# IMU_Core.net
KiCad netlist of a schematic drawn in Altium Designer
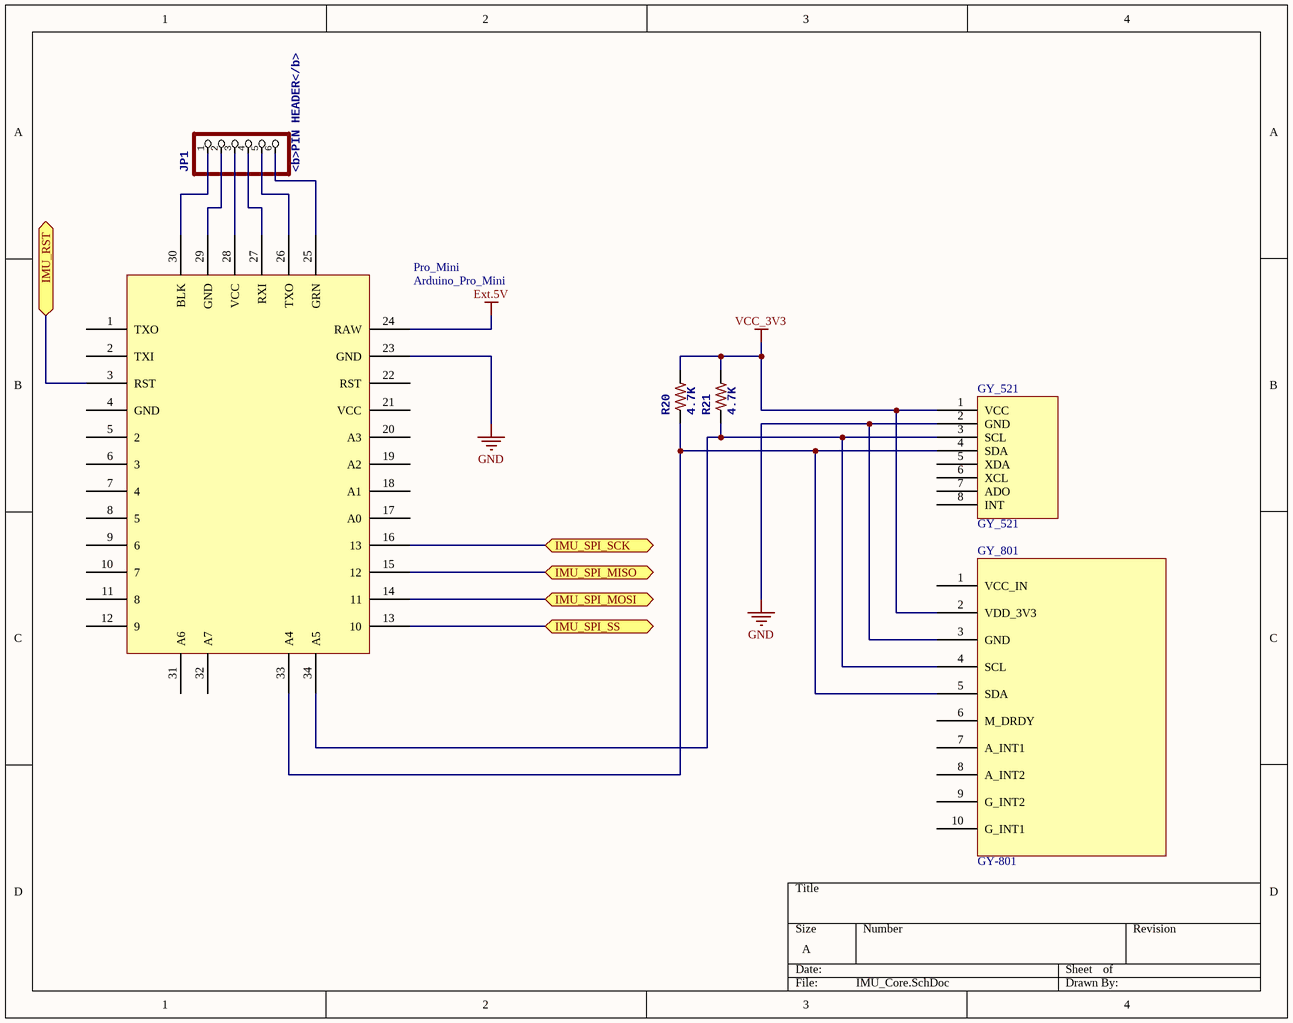
[diagram p0: IMU_Core.SchDoc]

(export (version "E")
  (design (tool "Eeschema 10.0.6"))
  (components
    (comp (ref "GY_521")
      (value "GY_521")
      (footprint "sensor_8pin")
      (libsource (lib "KLibrary") (part "GY_521"))
    )
    (comp (ref "GY_801")
      (value "GY-801")
      (footprint "Sensor_10Pin")
      (libsource (lib "KLibrary") (part "GY-801"))
    )
    (comp (ref "JP1")
      (value "<b>PIN HEADER</b>")
      (footprint "1X06")
      (libsource (lib "adafruit") (part "PINHD-1X6"))
    )
    (comp (ref "Pro_Mini")
      (value "Arduino_Pro_Mini")
      (footprint "Arduino_pro_mini")
      (libsource (lib "KLibrary") (part "Arduino_Pro_Mini"))
    )
    (comp (ref "R20") (value "4.7K") (footprint "R0805") (libsource (lib "adafruit") (part "R-US_R0805")))
    (comp (ref "R21") (value "4.7K") (footprint "R0805") (libsource (lib "adafruit") (part "R-US_R0805")))
  )
  (nets
    (net (code "1") (name "/IMU_RST") (class "Default")
      (node (ref "Pro_Mini") (pin "3") (pinfunction "RST_3") (pintype "passive"))
    )
    (net (code "2") (name "/IMU_SPI_MISO") (class "Default")
      (node (ref "Pro_Mini") (pin "15") (pinfunction "12_15") (pintype "passive"))
    )
    (net (code "3") (name "/IMU_SPI_MOSI") (class "Default")
      (node (ref "Pro_Mini") (pin "14") (pinfunction "11_14") (pintype "passive"))
    )
    (net (code "4") (name "/IMU_SPI_SCK") (class "Default")
      (node (ref "Pro_Mini") (pin "16") (pinfunction "13_16") (pintype "passive"))
    )
    (net (code "5") (name "/IMU_SPI_SS") (class "Default")
      (node (ref "Pro_Mini") (pin "13") (pinfunction "10_13") (pintype "passive"))
    )
    (net (code "6") (name "Ext.5V") (class "Default")
      (node (ref "Pro_Mini") (pin "24") (pinfunction "RAW_24") (pintype "passive"))
    )
    (net (code "7") (name "GND") (class "Default")
      (node (ref "GY_521") (pin "2") (pinfunction "GND_2") (pintype "passive"))
      (node (ref "GY_801") (pin "3") (pinfunction "GND_3") (pintype "passive"))
      (node (ref "Pro_Mini") (pin "23") (pinfunction "GND_23") (pintype "passive"))
    )
    (net (code "8") (name "Net-(GY_521-SCL)") (class "Default")
      (node (ref "GY_521") (pin "3") (pinfunction "SCL_3") (pintype "passive"))
      (node (ref "GY_801") (pin "4") (pinfunction "SCL_4") (pintype "passive"))
      (node (ref "Pro_Mini") (pin "34") (pinfunction "A5_34") (pintype "passive"))
      (node (ref "R21") (pin "1") (pinfunction "1_1") (pintype "passive"))
    )
    (net (code "9") (name "Net-(GY_521-SDA)") (class "Default")
      (node (ref "GY_521") (pin "4") (pinfunction "SDA_4") (pintype "passive"))
      (node (ref "GY_801") (pin "5") (pinfunction "SDA_5") (pintype "passive"))
      (node (ref "Pro_Mini") (pin "33") (pinfunction "A4_33") (pintype "passive"))
      (node (ref "R20") (pin "1") (pinfunction "1_1") (pintype "passive"))
    )
    (net (code "10") (name "Net-(JP1-Pad2)") (class "Default")
      (node (ref "JP1") (pin "2") (pinfunction "2_2") (pintype "passive"))
      (node (ref "Pro_Mini") (pin "29") (pinfunction "GND_29") (pintype "passive"))
    )
    (net (code "11") (name "Net-(JP1-Pad3)") (class "Default")
      (node (ref "JP1") (pin "3") (pinfunction "3_3") (pintype "passive"))
      (node (ref "Pro_Mini") (pin "28") (pinfunction "VCC_28") (pintype "passive"))
    )
    (net (code "12") (name "Net-(JP1-Pad5)") (class "Default")
      (node (ref "JP1") (pin "5") (pinfunction "5_5") (pintype "passive"))
      (node (ref "Pro_Mini") (pin "26") (pinfunction "TXO_26") (pintype "passive"))
    )
    (net (code "13") (name "Net-(Pro_Mini-BLK)") (class "Default")
      (node (ref "JP1") (pin "1") (pinfunction "1_1") (pintype "passive"))
      (node (ref "Pro_Mini") (pin "30") (pinfunction "BLK_30") (pintype "passive"))
    )
    (net (code "14") (name "Net-(Pro_Mini-GRN)") (class "Default")
      (node (ref "JP1") (pin "6") (pinfunction "6_6") (pintype "passive"))
      (node (ref "Pro_Mini") (pin "25") (pinfunction "GRN_25") (pintype "passive"))
    )
    (net (code "15") (name "Net-(Pro_Mini-RXI)") (class "Default")
      (node (ref "JP1") (pin "4") (pinfunction "4_4") (pintype "passive"))
      (node (ref "Pro_Mini") (pin "27") (pinfunction "RXI_27") (pintype "passive"))
    )
    (net (code "16") (name "VCC_3V3") (class "Default")
      (node (ref "GY_521") (pin "1") (pinfunction "VCC_1") (pintype "passive"))
      (node (ref "GY_801") (pin "2") (pinfunction "VDD_3V3_2") (pintype "passive"))
      (node (ref "R20") (pin "2") (pinfunction "2_2") (pintype "passive"))
      (node (ref "R21") (pin "2") (pinfunction "2_2") (pintype "passive"))
    )
    (net (code "17") (name "unconnected-(GY_521-ADO-Pad7)") (class "Default")
      (node (ref "GY_521") (pin "7") (pinfunction "ADO_7") (pintype "passive"))
    )
    (net (code "18") (name "unconnected-(GY_521-INT-Pad8)") (class "Default")
      (node (ref "GY_521") (pin "8") (pinfunction "INT_8") (pintype "passive"))
    )
    (net (code "19") (name "unconnected-(GY_521-XCL-Pad6)") (class "Default")
      (node (ref "GY_521") (pin "6") (pinfunction "XCL_6") (pintype "passive"))
    )
    (net (code "20") (name "unconnected-(GY_521-XDA-Pad5)") (class "Default")
      (node (ref "GY_521") (pin "5") (pinfunction "XDA_5") (pintype "passive"))
    )
    (net (code "21") (name "unconnected-(GY_801-A_INT1-Pad7)") (class "Default")
      (node (ref "GY_801") (pin "7") (pinfunction "A_INT1_7") (pintype "passive"))
    )
    (net (code "22") (name "unconnected-(GY_801-A_INT2-Pad8)") (class "Default")
      (node (ref "GY_801") (pin "8") (pinfunction "A_INT2_8") (pintype "passive"))
    )
    (net (code "23") (name "unconnected-(GY_801-G_INT1-Pad10)") (class "Default")
      (node (ref "GY_801") (pin "10") (pinfunction "G_INT1_10") (pintype "passive"))
    )
    (net (code "24") (name "unconnected-(GY_801-G_INT2-Pad9)") (class "Default")
      (node (ref "GY_801") (pin "9") (pinfunction "G_INT2_9") (pintype "passive"))
    )
    (net (code "25") (name "unconnected-(GY_801-M_DRDY-Pad6)") (class "Default")
      (node (ref "GY_801") (pin "6") (pinfunction "M_DRDY_6") (pintype "passive"))
    )
    (net (code "26") (name "unconnected-(GY_801-VCC_IN-Pad1)") (class "Default")
      (node (ref "GY_801") (pin "1") (pinfunction "VCC_IN_1") (pintype "passive"))
    )
    (net (code "27") (name "unconnected-(Pro_Mini-2-Pad5)") (class "Default")
      (node (ref "Pro_Mini") (pin "5") (pinfunction "2_5") (pintype "passive"))
    )
    (net (code "28") (name "unconnected-(Pro_Mini-3-Pad6)") (class "Default")
      (node (ref "Pro_Mini") (pin "6") (pinfunction "3_6") (pintype "passive"))
    )
    (net (code "29") (name "unconnected-(Pro_Mini-4-Pad7)") (class "Default")
      (node (ref "Pro_Mini") (pin "7") (pinfunction "4_7") (pintype "passive"))
    )
    (net (code "30") (name "unconnected-(Pro_Mini-5-Pad8)") (class "Default")
      (node (ref "Pro_Mini") (pin "8") (pinfunction "5_8") (pintype "passive"))
    )
    (net (code "31") (name "unconnected-(Pro_Mini-6-Pad9)") (class "Default")
      (node (ref "Pro_Mini") (pin "9") (pinfunction "6_9") (pintype "passive"))
    )
    (net (code "32") (name "unconnected-(Pro_Mini-7-Pad10)") (class "Default")
      (node (ref "Pro_Mini") (pin "10") (pinfunction "7_10") (pintype "passive"))
    )
    (net (code "33") (name "unconnected-(Pro_Mini-8-Pad11)") (class "Default")
      (node (ref "Pro_Mini") (pin "11") (pinfunction "8_11") (pintype "passive"))
    )
    (net (code "34") (name "unconnected-(Pro_Mini-9-Pad12)") (class "Default")
      (node (ref "Pro_Mini") (pin "12") (pinfunction "9_12") (pintype "passive"))
    )
    (net (code "35") (name "unconnected-(Pro_Mini-A0-Pad17)") (class "Default")
      (node (ref "Pro_Mini") (pin "17") (pinfunction "A0_17") (pintype "passive"))
    )
    (net (code "36") (name "unconnected-(Pro_Mini-A1-Pad18)") (class "Default")
      (node (ref "Pro_Mini") (pin "18") (pinfunction "A1_18") (pintype "passive"))
    )
    (net (code "37") (name "unconnected-(Pro_Mini-A2-Pad19)") (class "Default")
      (node (ref "Pro_Mini") (pin "19") (pinfunction "A2_19") (pintype "passive"))
    )
    (net (code "38") (name "unconnected-(Pro_Mini-A3-Pad20)") (class "Default")
      (node (ref "Pro_Mini") (pin "20") (pinfunction "A3_20") (pintype "passive"))
    )
    (net (code "39") (name "unconnected-(Pro_Mini-A6-Pad31)") (class "Default")
      (node (ref "Pro_Mini") (pin "31") (pinfunction "A6_31") (pintype "passive"))
    )
    (net (code "40") (name "unconnected-(Pro_Mini-A7-Pad32)") (class "Default")
      (node (ref "Pro_Mini") (pin "32") (pinfunction "A7_32") (pintype "passive"))
    )
    (net (code "41") (name "unconnected-(Pro_Mini-GND-Pad4)") (class "Default")
      (node (ref "Pro_Mini") (pin "4") (pinfunction "GND_4") (pintype "passive"))
    )
    (net (code "42") (name "unconnected-(Pro_Mini-RST-Pad22)") (class "Default")
      (node (ref "Pro_Mini") (pin "22") (pinfunction "RST_22") (pintype "passive"))
    )
    (net (code "43") (name "unconnected-(Pro_Mini-TXI-Pad2)") (class "Default")
      (node (ref "Pro_Mini") (pin "2") (pinfunction "TXI_2") (pintype "passive"))
    )
    (net (code "44") (name "unconnected-(Pro_Mini-TXO-Pad1)") (class "Default")
      (node (ref "Pro_Mini") (pin "1") (pinfunction "TXO_1") (pintype "passive"))
    )
    (net (code "45") (name "unconnected-(Pro_Mini-VCC-Pad21)") (class "Default")
      (node (ref "Pro_Mini") (pin "21") (pinfunction "VCC_21") (pintype "passive"))
    )
  )
)
